# Schematic_Measure_Temperature.net
KiCad netlist of a schematic drawn in EAGLE
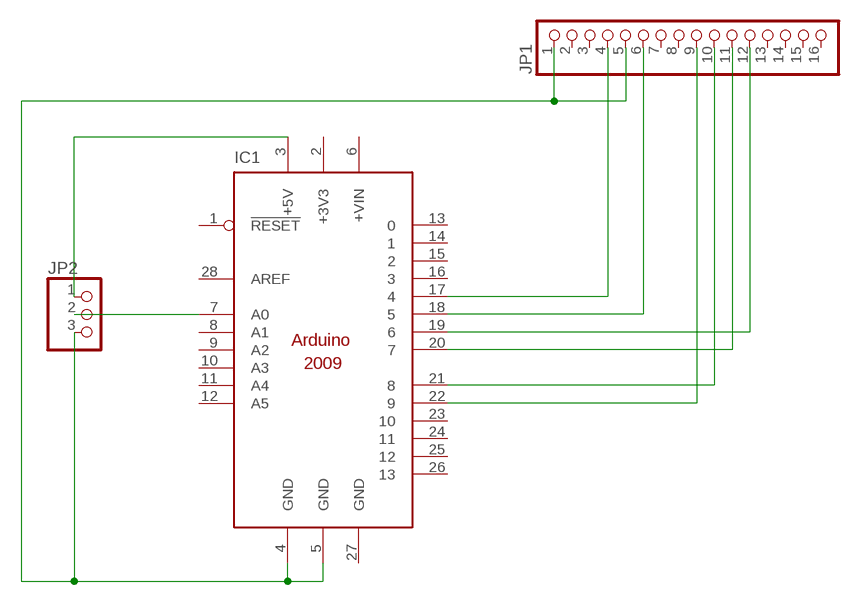
[diagram p0: schematic, sheet 1]

(export (version "E")
  (design (tool "Eeschema 10.0.6"))
  (components
    (comp (ref "IC1")
      (value "ARDUINO2009_12")
      (footprint "eagle-import:ARDUINO2009_2")
      (libsource (lib "eagle-import") (part "ARDUINO2009_12"))
    )
    (comp (ref "JP1")
      (value "PINHD-1X16")
      (footprint "eagle-import:1X16")
      (libsource (lib "eagle-import") (part "PINHD-1X16"))
    )
    (comp (ref "JP2")
      (value "PINHD-1X3")
      (footprint "eagle-import:1X03")
      (libsource (lib "eagle-import") (part "PINHD-1X3"))
    )
  )
  (nets
    (net (code "1") (name "/+3V3") (class "Default")
      (node (ref "IC1") (pin "2") (pinfunction "+3V3_2") (pintype "power_in"))
    )
    (net (code "2") (name "/GND") (class "Default")
      (node (ref "IC1") (pin "27") (pinfunction "GND_27") (pintype "power_in"))
    )
    (net (code "3") (name "Net-(IC1-+5V)") (class "Default")
      (node (ref "IC1") (pin "3") (pinfunction "+5V_3") (pintype "power_in"))
      (node (ref "JP2") (pin "1") (pinfunction "1_1") (pintype "passive"))
    )
    (net (code "4") (name "Net-(IC1-4)") (class "Default")
      (node (ref "IC1") (pin "17") (pinfunction "4_17") (pintype "bidirectional"))
      (node (ref "JP1") (pin "4") (pinfunction "4_4") (pintype "passive"))
    )
    (net (code "5") (name "Net-(IC1-5)") (class "Default")
      (node (ref "IC1") (pin "18") (pinfunction "5_18") (pintype "bidirectional"))
      (node (ref "JP1") (pin "6") (pinfunction "6_6") (pintype "passive"))
    )
    (net (code "6") (name "Net-(IC1-6)") (class "Default")
      (node (ref "IC1") (pin "19") (pinfunction "6_19") (pintype "bidirectional"))
      (node (ref "JP1") (pin "12") (pinfunction "12_12") (pintype "passive"))
    )
    (net (code "7") (name "Net-(IC1-7)") (class "Default")
      (node (ref "IC1") (pin "20") (pinfunction "7_20") (pintype "bidirectional"))
      (node (ref "JP1") (pin "11") (pinfunction "11_11") (pintype "passive"))
    )
    (net (code "8") (name "Net-(IC1-8)") (class "Default")
      (node (ref "IC1") (pin "21") (pinfunction "8_21") (pintype "bidirectional"))
      (node (ref "JP1") (pin "10") (pinfunction "10_10") (pintype "passive"))
    )
    (net (code "9") (name "Net-(IC1-9)") (class "Default")
      (node (ref "IC1") (pin "22") (pinfunction "9_22") (pintype "bidirectional"))
      (node (ref "JP1") (pin "9") (pinfunction "9_9") (pintype "passive"))
    )
    (net (code "10") (name "Net-(IC1-A0)") (class "Default")
      (node (ref "IC1") (pin "7") (pinfunction "A0_7") (pintype "bidirectional"))
      (node (ref "JP2") (pin "2") (pinfunction "2_2") (pintype "passive"))
    )
    (net (code "11") (name "Net-(IC1-GND-Pad4)") (class "Default")
      (node (ref "IC1") (pin "4") (pinfunction "GND_4") (pintype "power_in"))
      (node (ref "IC1") (pin "5") (pinfunction "GND_5") (pintype "power_in"))
      (node (ref "JP1") (pin "1") (pinfunction "1_1") (pintype "passive"))
      (node (ref "JP1") (pin "5") (pinfunction "5_5") (pintype "passive"))
      (node (ref "JP2") (pin "3") (pinfunction "3_3") (pintype "passive"))
    )
    (net (code "12") (name "unconnected-(IC1-+VIN-Pad6)") (class "Default")
      (node (ref "IC1") (pin "6") (pinfunction "+VIN_6") (pintype "bidirectional"))
    )
    (net (code "13") (name "unconnected-(IC1-0-Pad13)") (class "Default")
      (node (ref "IC1") (pin "13") (pinfunction "0_13") (pintype "bidirectional"))
    )
    (net (code "14") (name "unconnected-(IC1-1-Pad14)") (class "Default")
      (node (ref "IC1") (pin "14") (pinfunction "1_14") (pintype "bidirectional"))
    )
    (net (code "15") (name "unconnected-(IC1-2-Pad15)") (class "Default")
      (node (ref "IC1") (pin "15") (pinfunction "2_15") (pintype "bidirectional"))
    )
    (net (code "16") (name "unconnected-(IC1-3-Pad16)") (class "Default")
      (node (ref "IC1") (pin "16") (pinfunction "3_16") (pintype "bidirectional"))
    )
    (net (code "17") (name "unconnected-(IC1-10-Pad23)") (class "Default")
      (node (ref "IC1") (pin "23") (pinfunction "10_23") (pintype "bidirectional"))
    )
    (net (code "18") (name "unconnected-(IC1-11-Pad24)") (class "Default")
      (node (ref "IC1") (pin "24") (pinfunction "11_24") (pintype "bidirectional"))
    )
    (net (code "19") (name "unconnected-(IC1-12-Pad25)") (class "Default")
      (node (ref "IC1") (pin "25") (pinfunction "12_25") (pintype "bidirectional"))
    )
    (net (code "20") (name "unconnected-(IC1-13-Pad26)") (class "Default")
      (node (ref "IC1") (pin "26") (pinfunction "13_26") (pintype "bidirectional"))
    )
    (net (code "21") (name "unconnected-(IC1-A1-Pad8)") (class "Default")
      (node (ref "IC1") (pin "8") (pinfunction "A1_8") (pintype "bidirectional"))
    )
    (net (code "22") (name "unconnected-(IC1-A2-Pad9)") (class "Default")
      (node (ref "IC1") (pin "9") (pinfunction "A2_9") (pintype "bidirectional"))
    )
    (net (code "23") (name "unconnected-(IC1-A3-Pad10)") (class "Default")
      (node (ref "IC1") (pin "10") (pinfunction "A3_10") (pintype "bidirectional"))
    )
    (net (code "24") (name "unconnected-(IC1-A4-Pad11)") (class "Default")
      (node (ref "IC1") (pin "11") (pinfunction "A4_11") (pintype "bidirectional"))
    )
    (net (code "25") (name "unconnected-(IC1-A5-Pad12)") (class "Default")
      (node (ref "IC1") (pin "12") (pinfunction "A5_12") (pintype "bidirectional"))
    )
    (net (code "26") (name "unconnected-(IC1-AREF-Pad28)") (class "Default")
      (node (ref "IC1") (pin "28") (pinfunction "AREF_28") (pintype "bidirectional"))
    )
    (net (code "27") (name "unconnected-(IC1-~{RESET}-Pad1)") (class "Default")
      (node (ref "IC1") (pin "1") (pinfunction "~{RESET}_1") (pintype "bidirectional"))
    )
    (net (code "28") (name "unconnected-(JP1-Pad2)") (class "Default")
      (node (ref "JP1") (pin "2") (pinfunction "2_2") (pintype "passive"))
    )
    (net (code "29") (name "unconnected-(JP1-Pad3)") (class "Default")
      (node (ref "JP1") (pin "3") (pinfunction "3_3") (pintype "passive"))
    )
    (net (code "30") (name "unconnected-(JP1-Pad7)") (class "Default")
      (node (ref "JP1") (pin "7") (pinfunction "7_7") (pintype "passive"))
    )
    (net (code "31") (name "unconnected-(JP1-Pad8)") (class "Default")
      (node (ref "JP1") (pin "8") (pinfunction "8_8") (pintype "passive"))
    )
    (net (code "32") (name "unconnected-(JP1-Pad13)") (class "Default")
      (node (ref "JP1") (pin "13") (pinfunction "13_13") (pintype "passive"))
    )
    (net (code "33") (name "unconnected-(JP1-Pad14)") (class "Default")
      (node (ref "JP1") (pin "14") (pinfunction "14_14") (pintype "passive"))
    )
    (net (code "34") (name "unconnected-(JP1-Pad15)") (class "Default")
      (node (ref "JP1") (pin "15") (pinfunction "15_15") (pintype "passive"))
    )
    (net (code "35") (name "unconnected-(JP1-Pad16)") (class "Default")
      (node (ref "JP1") (pin "16") (pinfunction "16_16") (pintype "passive"))
    )
  )
)
